# HelvePicV2_0fSMD.net
KiCad netlist of a schematic drawn in EAGLE
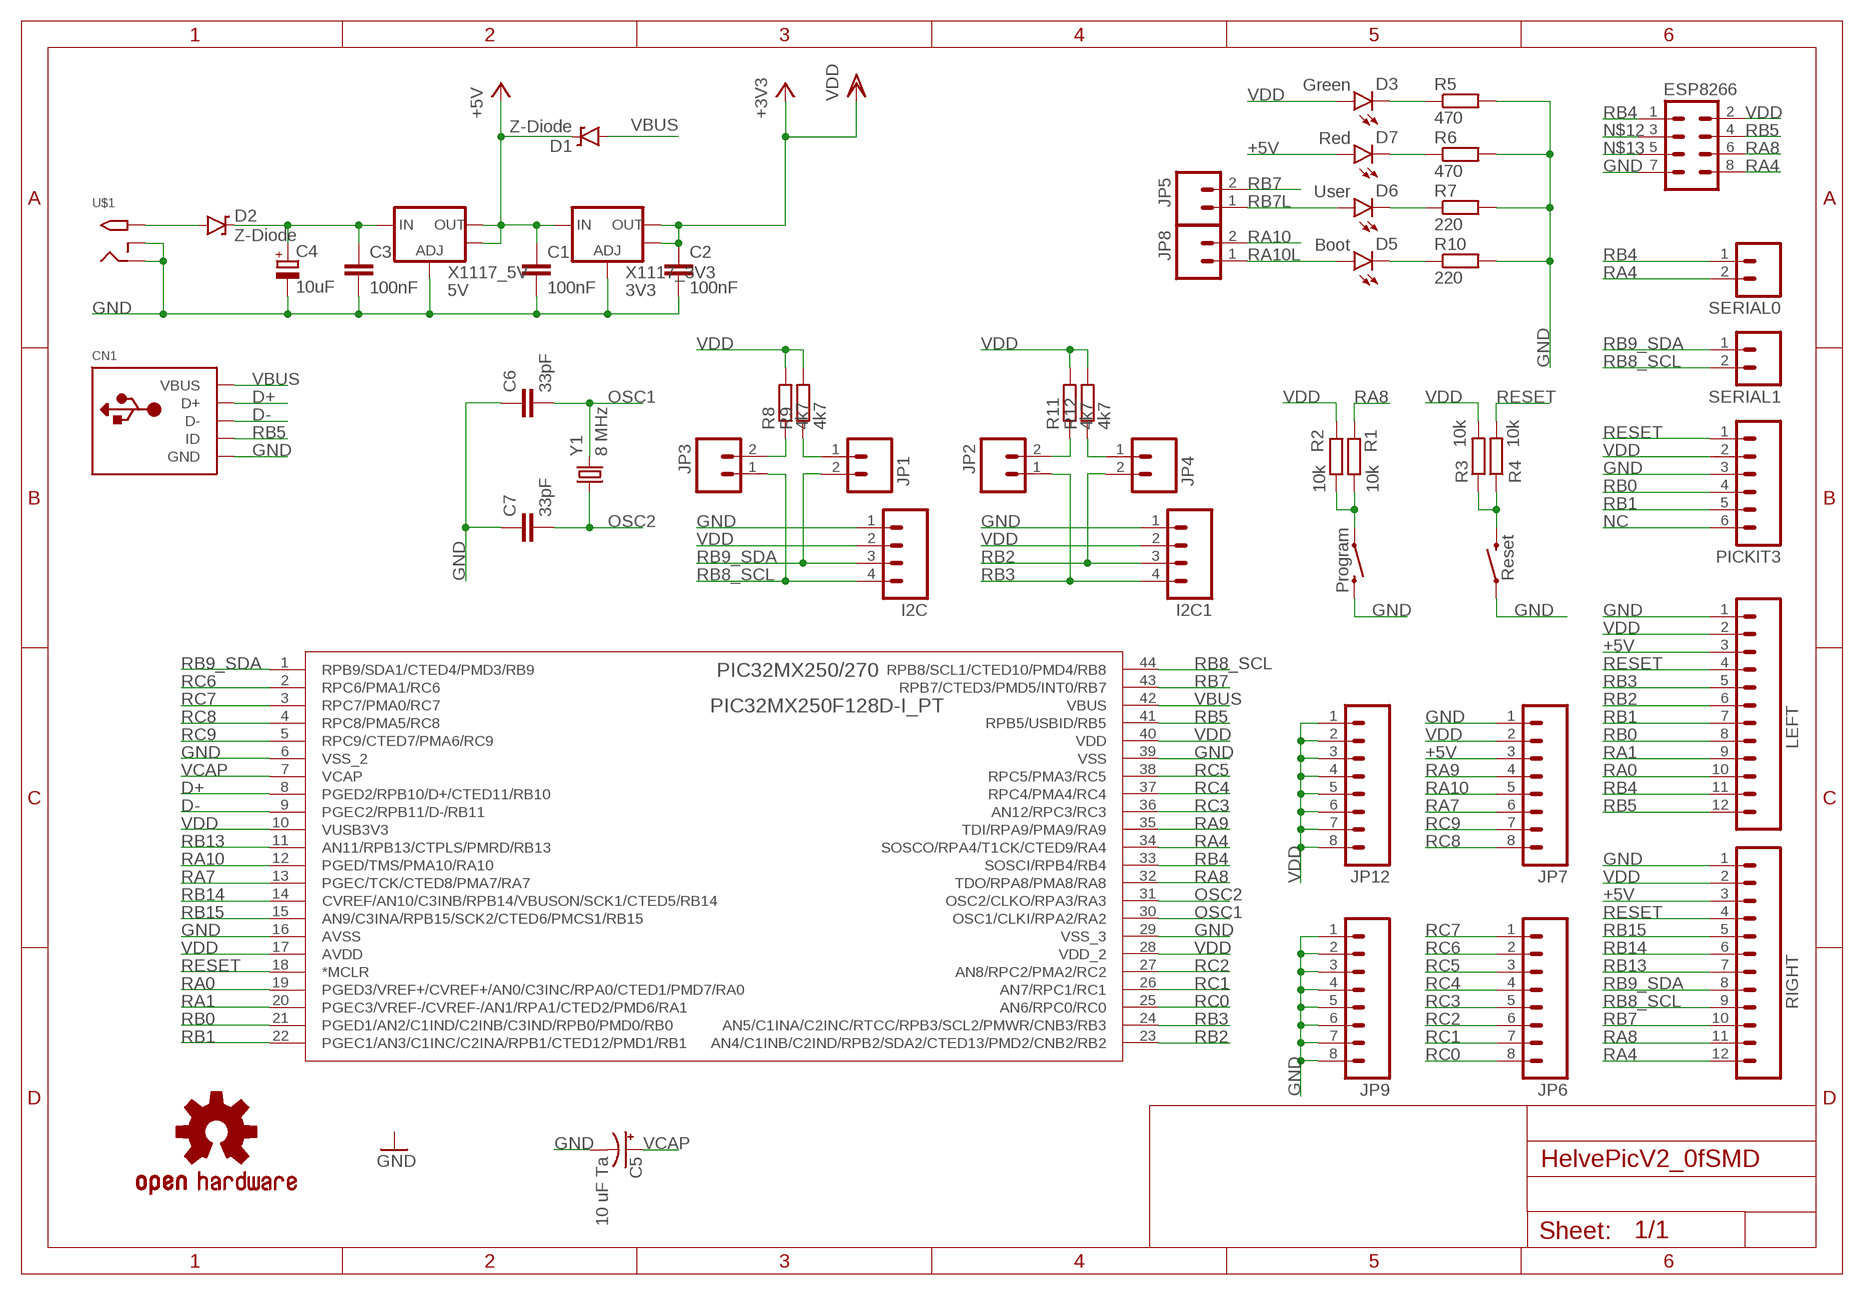
[diagram p0: schematic, sheet 1]

(export (version "E")
  (design (tool "Eeschema 10.0.6"))
  (components
    (comp (ref "C1")
      (value "100nF")
      (footprint "eagle-import:C1206")
      (libsource (lib "eagle-import") (part "C-EUC1206"))
    )
    (comp (ref "C2")
      (value "100nF")
      (footprint "eagle-import:C1206")
      (libsource (lib "eagle-import") (part "C-EUC1206"))
    )
    (comp (ref "C3")
      (value "100nF")
      (footprint "eagle-import:C1206")
      (libsource (lib "eagle-import") (part "C-EUC1206"))
    )
    (comp (ref "C4")
      (value "10uF")
      (footprint "eagle-import:153CLV-0810")
      (libsource (lib "eagle-import") (part "CPOL-EU153CLV-0810"))
    )
    (comp (ref "C5")
      (value "10 uF Ta")
      (footprint "eagle-import:EIA3216")
      (libsource (lib "eagle-import") (part "CAP_POL1206"))
    )
    (comp (ref "C6")
      (value "33pF")
      (footprint "eagle-import:C1206")
      (libsource (lib "eagle-import") (part "C-EUC1206"))
    )
    (comp (ref "C7")
      (value "33pF")
      (footprint "eagle-import:C1206")
      (libsource (lib "eagle-import") (part "C-EUC1206"))
    )
    (comp (ref "CN1")
      (value "USBMINIB")
      (footprint "eagle-import:USB-MINIB")
      (libsource (lib "eagle-import") (part "USBMINIB"))
    )
    (comp (ref "D1")
      (value "Z-Diode")
      (footprint "eagle-import:SMB-DIODE")
      (libsource (lib "eagle-import") (part "DIODE-ZENERSMB"))
    )
    (comp (ref "D2")
      (value "Z-Diode")
      (footprint "eagle-import:SMB-DIODE")
      (libsource (lib "eagle-import") (part "DIODE-ZENERSMB"))
    )
    (comp (ref "D3")
      (value "Green")
      (footprint "eagle-import:LED-1206")
      (libsource (lib "eagle-import") (part "LED1206"))
    )
    (comp (ref "D5")
      (value "Boot")
      (footprint "eagle-import:LED-1206")
      (libsource (lib "eagle-import") (part "LED1206"))
    )
    (comp (ref "D6")
      (value "User")
      (footprint "eagle-import:LED-1206")
      (libsource (lib "eagle-import") (part "LED1206"))
    )
    (comp (ref "D7")
      (value "Red")
      (footprint "eagle-import:LED-1206")
      (libsource (lib "eagle-import") (part "LED1206"))
    )
    (comp (ref "ESP8266")
      (value "M04X2")
      (footprint "eagle-import:2X4")
      (libsource (lib "eagle-import") (part "M04X2"))
    )
    (comp (ref "I2C")
      (value "M04PTH")
      (footprint "eagle-import:1X04")
      (libsource (lib "eagle-import") (part "M04PTH"))
    )
    (comp (ref "I2C1")
      (value "M04PTH")
      (footprint "eagle-import:1X04")
      (libsource (lib "eagle-import") (part "M04PTH"))
    )
    (comp (ref "JP1")
      (value "M02PTH")
      (footprint "eagle-import:1X02")
      (libsource (lib "eagle-import") (part "M02PTH"))
    )
    (comp (ref "JP2")
      (value "M02PTH")
      (footprint "eagle-import:1X02")
      (libsource (lib "eagle-import") (part "M02PTH"))
    )
    (comp (ref "JP3")
      (value "M02PTH")
      (footprint "eagle-import:1X02")
      (libsource (lib "eagle-import") (part "M02PTH"))
    )
    (comp (ref "JP4")
      (value "M02PTH")
      (footprint "eagle-import:1X02")
      (libsource (lib "eagle-import") (part "M02PTH"))
    )
    (comp (ref "JP5")
      (value "M02PTH")
      (footprint "eagle-import:1X02")
      (libsource (lib "eagle-import") (part "M02PTH"))
    )
    (comp (ref "JP6")
      (value "M081X08")
      (footprint "eagle-import:1X08")
      (libsource (lib "eagle-import") (part "M081X08"))
    )
    (comp (ref "JP7")
      (value "M081X08")
      (footprint "eagle-import:1X08")
      (libsource (lib "eagle-import") (part "M081X08"))
    )
    (comp (ref "JP8")
      (value "M02PTH")
      (footprint "eagle-import:1X02")
      (libsource (lib "eagle-import") (part "M02PTH"))
    )
    (comp (ref "JP9")
      (value "M081X08")
      (footprint "eagle-import:1X08")
      (libsource (lib "eagle-import") (part "M081X08"))
    )
    (comp (ref "JP12")
      (value "M081X08")
      (footprint "eagle-import:1X08")
      (libsource (lib "eagle-import") (part "M081X08"))
    )
    (comp (ref "LEFT")
      (value "M12PTH")
      (footprint "eagle-import:1X12")
      (libsource (lib "eagle-import") (part "M12PTH"))
    )
    (comp (ref "LOGO1")
      (value "OSHW-LOGOS")
      (footprint "eagle-import:OSHW-LOGO-S")
      (libsource (lib "eagle-import") (part "OSHW-LOGOS"))
    )
    (comp (ref "PIC32MX250/270")
      (value "PIC32MX250F128D-I_PT")
      (footprint "eagle-import:QFP44_10X10MC")
      (libsource (lib "eagle-import") (part "PIC32MX250F128D-I_PT"))
    )
    (comp (ref "PICKIT3")
      (value "M06LOCK")
      (footprint "eagle-import:1X06_LOCK")
      (libsource (lib "eagle-import") (part "M06LOCK"))
    )
    (comp (ref "R1")
      (value "10k")
      (footprint "eagle-import:R1206")
      (libsource (lib "eagle-import") (part "R-EU_R1206"))
    )
    (comp (ref "R2")
      (value "10k")
      (footprint "eagle-import:R1206")
      (libsource (lib "eagle-import") (part "R-EU_R1206"))
    )
    (comp (ref "R3")
      (value "10k")
      (footprint "eagle-import:R1206")
      (libsource (lib "eagle-import") (part "R-EU_R1206"))
    )
    (comp (ref "R4")
      (value "10k")
      (footprint "eagle-import:R1206")
      (libsource (lib "eagle-import") (part "R-EU_R1206"))
    )
    (comp (ref "R5")
      (value "470")
      (footprint "eagle-import:R1206")
      (libsource (lib "eagle-import") (part "R-EU_R1206"))
    )
    (comp (ref "R6")
      (value "470")
      (footprint "eagle-import:R1206")
      (libsource (lib "eagle-import") (part "R-EU_R1206"))
    )
    (comp (ref "R7")
      (value "220")
      (footprint "eagle-import:R1206")
      (libsource (lib "eagle-import") (part "R-EU_R1206"))
    )
    (comp (ref "R8")
      (value "4k7")
      (footprint "eagle-import:R1206")
      (libsource (lib "eagle-import") (part "R-EU_R1206"))
    )
    (comp (ref "R9")
      (value "4k7")
      (footprint "eagle-import:R1206")
      (libsource (lib "eagle-import") (part "R-EU_R1206"))
    )
    (comp (ref "R10")
      (value "220")
      (footprint "eagle-import:R1206")
      (libsource (lib "eagle-import") (part "R-EU_R1206"))
    )
    (comp (ref "R11")
      (value "4k7")
      (footprint "eagle-import:R1206")
      (libsource (lib "eagle-import") (part "R-EU_R1206"))
    )
    (comp (ref "R12")
      (value "4k7")
      (footprint "eagle-import:R1206")
      (libsource (lib "eagle-import") (part "R-EU_R1206"))
    )
    (comp (ref "RIGHT")
      (value "M12PTH")
      (footprint "eagle-import:1X12")
      (libsource (lib "eagle-import") (part "M12PTH"))
    )
    (comp (ref "S1")
      (value "Program")
      (footprint "eagle-import:TACTILE_SWITCH_TALL")
      (libsource (lib "eagle-import") (part "SWITCH-MOMENTARY-2SMD-4"))
    )
    (comp (ref "S3")
      (value "Reset")
      (footprint "eagle-import:TACTILE_SWITCH_TALL")
      (libsource (lib "eagle-import") (part "SWITCH-MOMENTARY-2SMD-4"))
    )
    (comp (ref "SERIAL0")
      (value "M02PTH")
      (footprint "eagle-import:1X02")
      (libsource (lib "eagle-import") (part "M02PTH"))
    )
    (comp (ref "SERIAL1")
      (value "M02PTH")
      (footprint "eagle-import:1X02")
      (libsource (lib "eagle-import") (part "M02PTH"))
    )
    (comp (ref "U$1")
      (value "2.1MMJACKTHM")
      (footprint "eagle-import:PJ-102A")
      (libsource (lib "eagle-import") (part "2.1MMJACKTHM"))
    )
    (comp (ref "X1117_3V3")
      (value "3V3")
      (footprint "eagle-import:SOT223")
      (libsource (lib "eagle-import") (part "V_REG_LM1117SOT223"))
    )
    (comp (ref "X1117_5V")
      (value "5V")
      (footprint "eagle-import:SOT223")
      (libsource (lib "eagle-import") (part "V_REG_LM1117SOT223"))
    )
    (comp (ref "Y1")
      (value "8 MHz")
      (footprint "eagle-import:HC49UP")
      (libsource (lib "eagle-import") (part "CRYSTALSMD"))
    )
  )
  (nets
    (net (code "1") (name "+3V3") (class "Default")
      (node (ref "C2") (pin "1") (pinfunction "1_1") (pintype "passive"))
      (node (ref "D3") (pin "A") (pinfunction "A_A") (pintype "passive"))
      (node (ref "ESP8266") (pin "2") (pinfunction "2_2") (pintype "passive"))
      (node (ref "I2C") (pin "2") (pinfunction "2_2") (pintype "passive"))
      (node (ref "I2C1") (pin "2") (pinfunction "2_2") (pintype "passive"))
      (node (ref "JP12") (pin "1") (pinfunction "1_1") (pintype "passive"))
      (node (ref "JP12") (pin "2") (pinfunction "2_2") (pintype "passive"))
      (node (ref "JP12") (pin "3") (pinfunction "3_3") (pintype "passive"))
      (node (ref "JP12") (pin "4") (pinfunction "4_4") (pintype "passive"))
      (node (ref "JP12") (pin "5") (pinfunction "5_5") (pintype "passive"))
      (node (ref "JP12") (pin "6") (pinfunction "6_6") (pintype "passive"))
      (node (ref "JP12") (pin "7") (pinfunction "7_7") (pintype "passive"))
      (node (ref "JP12") (pin "8") (pinfunction "8_8") (pintype "passive"))
      (node (ref "JP7") (pin "2") (pinfunction "2_2") (pintype "passive"))
      (node (ref "LEFT") (pin "2") (pinfunction "2_2") (pintype "passive"))
      (node (ref "PIC32MX250/270") (pin "10") (pinfunction "VUSB3V3_10") (pintype "bidirectional"))
      (node (ref "PIC32MX250/270") (pin "17") (pinfunction "AVDD_17") (pintype "power_in"))
      (node (ref "PIC32MX250/270") (pin "28") (pinfunction "VDD_2_28") (pintype "power_in"))
      (node (ref "PIC32MX250/270") (pin "40") (pinfunction "VDD_40") (pintype "power_in"))
      (node (ref "PICKIT3") (pin "2") (pinfunction "2_2") (pintype "passive"))
      (node (ref "R11") (pin "2") (pinfunction "2_2") (pintype "passive"))
      (node (ref "R12") (pin "2") (pinfunction "2_2") (pintype "passive"))
      (node (ref "R2") (pin "1") (pinfunction "1_1") (pintype "passive"))
      (node (ref "R3") (pin "2") (pinfunction "2_2") (pintype "passive"))
      (node (ref "R8") (pin "2") (pinfunction "2_2") (pintype "passive"))
      (node (ref "R9") (pin "2") (pinfunction "2_2") (pintype "passive"))
      (node (ref "RIGHT") (pin "2") (pinfunction "2_2") (pintype "passive"))
      (node (ref "X1117_3V3") (pin "2") (pinfunction "OUT_2") (pintype "output"))
      (node (ref "X1117_3V3") (pin "4") (pinfunction "OUT_4") (pintype "output"))
    )
    (net (code "2") (name "+5V") (class "Default")
      (node (ref "C1") (pin "1") (pinfunction "1_1") (pintype "passive"))
      (node (ref "D1") (pin "C") (pinfunction "C_C") (pintype "passive"))
      (node (ref "D7") (pin "A") (pinfunction "A_A") (pintype "passive"))
      (node (ref "JP7") (pin "3") (pinfunction "3_3") (pintype "passive"))
      (node (ref "LEFT") (pin "3") (pinfunction "3_3") (pintype "passive"))
      (node (ref "RIGHT") (pin "3") (pinfunction "3_3") (pintype "passive"))
      (node (ref "X1117_3V3") (pin "3") (pinfunction "IN_3") (pintype "input"))
      (node (ref "X1117_5V") (pin "2") (pinfunction "OUT_2") (pintype "output"))
      (node (ref "X1117_5V") (pin "4") (pinfunction "OUT_4") (pintype "output"))
    )
    (net (code "3") (name "/D+") (class "Default")
      (node (ref "CN1") (pin "D+") (pinfunction "D+_D+") (pintype "bidirectional"))
      (node (ref "PIC32MX250/270") (pin "8") (pinfunction "PGED2/RPB10/D+/CTED11/RB10_8") (pintype "bidirectional"))
    )
    (net (code "4") (name "/D-") (class "Default")
      (node (ref "CN1") (pin "D-") (pinfunction "D-_D-") (pintype "bidirectional"))
      (node (ref "PIC32MX250/270") (pin "9") (pinfunction "PGEC2/RPB11/D-/RB11_9") (pintype "bidirectional"))
    )
    (net (code "5") (name "/N$12") (class "Default")
      (node (ref "ESP8266") (pin "3") (pinfunction "3_3") (pintype "passive"))
    )
    (net (code "6") (name "/N$13") (class "Default")
      (node (ref "ESP8266") (pin "5") (pinfunction "5_5") (pintype "passive"))
    )
    (net (code "7") (name "/NC") (class "Default")
      (node (ref "PICKIT3") (pin "6") (pinfunction "6_6") (pintype "passive"))
    )
    (net (code "8") (name "/OSC1") (class "Default")
      (node (ref "C6") (pin "2") (pinfunction "2_2") (pintype "passive"))
      (node (ref "PIC32MX250/270") (pin "30") (pinfunction "OSC1/CLKI/RPA2/RA2_30") (pintype "bidirectional"))
      (node (ref "Y1") (pin "2") (pinfunction "2_2") (pintype "passive"))
    )
    (net (code "9") (name "/OSC2") (class "Default")
      (node (ref "C7") (pin "2") (pinfunction "2_2") (pintype "passive"))
      (node (ref "PIC32MX250/270") (pin "31") (pinfunction "OSC2/CLKO/RPA3/RA3_31") (pintype "bidirectional"))
      (node (ref "Y1") (pin "1") (pinfunction "1_1") (pintype "passive"))
    )
    (net (code "10") (name "/RA0") (class "Default")
      (node (ref "LEFT") (pin "10") (pinfunction "10_10") (pintype "passive"))
      (node (ref "PIC32MX250/270") (pin "19") (pinfunction "PGED3/VREF+/CVREF+/AN0/C3INC/RPA0/CTED1/PMD7/RA0_19") (pintype "bidirectional"))
    )
    (net (code "11") (name "/RA1") (class "Default")
      (node (ref "LEFT") (pin "9") (pinfunction "9_9") (pintype "passive"))
      (node (ref "PIC32MX250/270") (pin "20") (pinfunction "PGEC3/VREF-/CVREF-/AN1/RPA1/CTED2/PMD6/RA1_20") (pintype "bidirectional"))
    )
    (net (code "12") (name "/RA4") (class "Default")
      (node (ref "ESP8266") (pin "8") (pinfunction "8_8") (pintype "passive"))
      (node (ref "PIC32MX250/270") (pin "34") (pinfunction "SOSCO/RPA4/T1CK/CTED9/RA4_34") (pintype "bidirectional"))
      (node (ref "RIGHT") (pin "12") (pinfunction "12_12") (pintype "passive"))
      (node (ref "SERIAL0") (pin "2") (pinfunction "2_2") (pintype "passive"))
    )
    (net (code "13") (name "/RA7") (class "Default")
      (node (ref "JP7") (pin "6") (pinfunction "6_6") (pintype "passive"))
      (node (ref "PIC32MX250/270") (pin "13") (pinfunction "PGEC/TCK/CTED8/PMA7/RA7_13") (pintype "bidirectional"))
    )
    (net (code "14") (name "/RA8") (class "Default")
      (node (ref "ESP8266") (pin "6") (pinfunction "6_6") (pintype "passive"))
      (node (ref "PIC32MX250/270") (pin "32") (pinfunction "TDO/RPA8/PMA8/RA8_32") (pintype "bidirectional"))
      (node (ref "R1") (pin "1") (pinfunction "1_1") (pintype "passive"))
      (node (ref "RIGHT") (pin "11") (pinfunction "11_11") (pintype "passive"))
    )
    (net (code "15") (name "/RA9") (class "Default")
      (node (ref "JP7") (pin "4") (pinfunction "4_4") (pintype "passive"))
      (node (ref "PIC32MX250/270") (pin "35") (pinfunction "TDI/RPA9/PMA9/RA9_35") (pintype "bidirectional"))
    )
    (net (code "16") (name "/RA10") (class "Default")
      (node (ref "JP7") (pin "5") (pinfunction "5_5") (pintype "passive"))
      (node (ref "JP8") (pin "2") (pinfunction "2_2") (pintype "passive"))
      (node (ref "PIC32MX250/270") (pin "12") (pinfunction "PGED/TMS/PMA10/RA10_12") (pintype "bidirectional"))
    )
    (net (code "17") (name "/RA10L") (class "Default")
      (node (ref "D5") (pin "A") (pinfunction "A_A") (pintype "passive"))
      (node (ref "JP8") (pin "1") (pinfunction "1_1") (pintype "passive"))
    )
    (net (code "18") (name "/RB0") (class "Default")
      (node (ref "LEFT") (pin "8") (pinfunction "8_8") (pintype "passive"))
      (node (ref "PIC32MX250/270") (pin "21") (pinfunction "PGED1/AN2/C1IND/C2INB/C3IND/RPB0/PMD0/RB0_21") (pintype "bidirectional"))
      (node (ref "PICKIT3") (pin "4") (pinfunction "4_4") (pintype "passive"))
    )
    (net (code "19") (name "/RB1") (class "Default")
      (node (ref "LEFT") (pin "7") (pinfunction "7_7") (pintype "passive"))
      (node (ref "PIC32MX250/270") (pin "22") (pinfunction "PGEC1/AN3/C1INC/C2INA/RPB1/CTED12/PMD1/RB1_22") (pintype "bidirectional"))
      (node (ref "PICKIT3") (pin "5") (pinfunction "5_5") (pintype "passive"))
    )
    (net (code "20") (name "/RB2") (class "Default")
      (node (ref "I2C1") (pin "3") (pinfunction "3_3") (pintype "passive"))
      (node (ref "JP4") (pin "2") (pinfunction "2_2") (pintype "passive"))
      (node (ref "LEFT") (pin "6") (pinfunction "6_6") (pintype "passive"))
      (node (ref "PIC32MX250/270") (pin "23") (pinfunction "AN4/C1INB/C2IND/RPB2/SDA2/CTED13/PMD2/CNB2/RB2_23") (pintype "bidirectional"))
    )
    (net (code "21") (name "/RB3") (class "Default")
      (node (ref "I2C1") (pin "4") (pinfunction "4_4") (pintype "passive"))
      (node (ref "JP2") (pin "1") (pinfunction "1_1") (pintype "passive"))
      (node (ref "LEFT") (pin "5") (pinfunction "5_5") (pintype "passive"))
      (node (ref "PIC32MX250/270") (pin "24") (pinfunction "AN5/C1INA/C2INC/RTCC/RPB3/SCL2/PMWR/CNB3/RB3_24") (pintype "bidirectional"))
    )
    (net (code "22") (name "/RB4") (class "Default")
      (node (ref "ESP8266") (pin "1") (pinfunction "1_1") (pintype "passive"))
      (node (ref "LEFT") (pin "11") (pinfunction "11_11") (pintype "passive"))
      (node (ref "PIC32MX250/270") (pin "33") (pinfunction "SOSCI/RPB4/RB4_33") (pintype "bidirectional"))
      (node (ref "SERIAL0") (pin "1") (pinfunction "1_1") (pintype "passive"))
    )
    (net (code "23") (name "/RB5") (class "Default")
      (node (ref "CN1") (pin "ID") (pinfunction "ID_ID") (pintype "bidirectional"))
      (node (ref "ESP8266") (pin "4") (pinfunction "4_4") (pintype "passive"))
      (node (ref "LEFT") (pin "12") (pinfunction "12_12") (pintype "passive"))
      (node (ref "PIC32MX250/270") (pin "41") (pinfunction "RPB5/USBID/RB5_41") (pintype "bidirectional"))
    )
    (net (code "24") (name "/RB7") (class "Default")
      (node (ref "JP5") (pin "2") (pinfunction "2_2") (pintype "passive"))
      (node (ref "PIC32MX250/270") (pin "43") (pinfunction "RPB7/CTED3/PMD5/INT0/RB7_43") (pintype "bidirectional"))
      (node (ref "RIGHT") (pin "10") (pinfunction "10_10") (pintype "passive"))
    )
    (net (code "25") (name "/RB7L") (class "Default")
      (node (ref "D6") (pin "A") (pinfunction "A_A") (pintype "passive"))
      (node (ref "JP5") (pin "1") (pinfunction "1_1") (pintype "passive"))
    )
    (net (code "26") (name "/RB8_SCL") (class "Default")
      (node (ref "I2C") (pin "4") (pinfunction "4_4") (pintype "passive"))
      (node (ref "JP3") (pin "1") (pinfunction "1_1") (pintype "passive"))
      (node (ref "PIC32MX250/270") (pin "44") (pinfunction "RPB8/SCL1/CTED10/PMD4/RB8_44") (pintype "bidirectional"))
      (node (ref "RIGHT") (pin "9") (pinfunction "9_9") (pintype "passive"))
      (node (ref "SERIAL1") (pin "2") (pinfunction "2_2") (pintype "passive"))
    )
    (net (code "27") (name "/RB9_SDA") (class "Default")
      (node (ref "I2C") (pin "3") (pinfunction "3_3") (pintype "passive"))
      (node (ref "JP1") (pin "2") (pinfunction "2_2") (pintype "passive"))
      (node (ref "PIC32MX250/270") (pin "1") (pinfunction "RPB9/SDA1/CTED4/PMD3/RB9_1") (pintype "bidirectional"))
      (node (ref "RIGHT") (pin "8") (pinfunction "8_8") (pintype "passive"))
      (node (ref "SERIAL1") (pin "1") (pinfunction "1_1") (pintype "passive"))
    )
    (net (code "28") (name "/RB13") (class "Default")
      (node (ref "PIC32MX250/270") (pin "11") (pinfunction "AN11/RPB13/CTPLS/PMRD/RB13_11") (pintype "bidirectional"))
      (node (ref "RIGHT") (pin "7") (pinfunction "7_7") (pintype "passive"))
    )
    (net (code "29") (name "/RB14") (class "Default")
      (node (ref "PIC32MX250/270") (pin "14") (pinfunction "CVREF/AN10/C3INB/RPB14/VBUSON/SCK1/CTED5/RB14_14") (pintype "bidirectional"))
      (node (ref "RIGHT") (pin "6") (pinfunction "6_6") (pintype "passive"))
    )
    (net (code "30") (name "/RB15") (class "Default")
      (node (ref "PIC32MX250/270") (pin "15") (pinfunction "AN9/C3INA/RPB15/SCK2/CTED6/PMCS1/RB15_15") (pintype "bidirectional"))
      (node (ref "RIGHT") (pin "5") (pinfunction "5_5") (pintype "passive"))
    )
    (net (code "31") (name "/RC0") (class "Default")
      (node (ref "JP6") (pin "8") (pinfunction "8_8") (pintype "passive"))
      (node (ref "PIC32MX250/270") (pin "25") (pinfunction "AN6/RPC0/RC0_25") (pintype "bidirectional"))
    )
    (net (code "32") (name "/RC1") (class "Default")
      (node (ref "JP6") (pin "7") (pinfunction "7_7") (pintype "passive"))
      (node (ref "PIC32MX250/270") (pin "26") (pinfunction "AN7/RPC1/RC1_26") (pintype "bidirectional"))
    )
    (net (code "33") (name "/RC2") (class "Default")
      (node (ref "JP6") (pin "6") (pinfunction "6_6") (pintype "passive"))
      (node (ref "PIC32MX250/270") (pin "27") (pinfunction "AN8/RPC2/PMA2/RC2_27") (pintype "bidirectional"))
    )
    (net (code "34") (name "/RC3") (class "Default")
      (node (ref "JP6") (pin "5") (pinfunction "5_5") (pintype "passive"))
      (node (ref "PIC32MX250/270") (pin "36") (pinfunction "AN12/RPC3/RC3_36") (pintype "bidirectional"))
    )
    (net (code "35") (name "/RC4") (class "Default")
      (node (ref "JP6") (pin "4") (pinfunction "4_4") (pintype "passive"))
      (node (ref "PIC32MX250/270") (pin "37") (pinfunction "RPC4/PMA4/RC4_37") (pintype "bidirectional"))
    )
    (net (code "36") (name "/RC5") (class "Default")
      (node (ref "JP6") (pin "3") (pinfunction "3_3") (pintype "passive"))
      (node (ref "PIC32MX250/270") (pin "38") (pinfunction "RPC5/PMA3/RC5_38") (pintype "bidirectional"))
    )
    (net (code "37") (name "/RC6") (class "Default")
      (node (ref "JP6") (pin "2") (pinfunction "2_2") (pintype "passive"))
      (node (ref "PIC32MX250/270") (pin "2") (pinfunction "RPC6/PMA1/RC6_2") (pintype "bidirectional"))
    )
    (net (code "38") (name "/RC7") (class "Default")
      (node (ref "JP6") (pin "1") (pinfunction "1_1") (pintype "passive"))
      (node (ref "PIC32MX250/270") (pin "3") (pinfunction "RPC7/PMA0/RC7_3") (pintype "bidirectional"))
    )
    (net (code "39") (name "/RC8") (class "Default")
      (node (ref "JP7") (pin "8") (pinfunction "8_8") (pintype "passive"))
      (node (ref "PIC32MX250/270") (pin "4") (pinfunction "RPC8/PMA5/RC8_4") (pintype "bidirectional"))
    )
    (net (code "40") (name "/RC9") (class "Default")
      (node (ref "JP7") (pin "7") (pinfunction "7_7") (pintype "passive"))
      (node (ref "PIC32MX250/270") (pin "5") (pinfunction "RPC9/CTED7/PMA6/RC9_5") (pintype "bidirectional"))
    )
    (net (code "41") (name "/RESET") (class "Default")
      (node (ref "LEFT") (pin "4") (pinfunction "4_4") (pintype "passive"))
      (node (ref "PIC32MX250/270") (pin "18") (pinfunction "*MCLR_18") (pintype "input"))
      (node (ref "PICKIT3") (pin "1") (pinfunction "1_1") (pintype "passive"))
      (node (ref "R4") (pin "2") (pinfunction "2_2") (pintype "passive"))
      (node (ref "RIGHT") (pin "4") (pinfunction "4_4") (pintype "passive"))
    )
    (net (code "42") (name "/VBUS") (class "Default")
      (node (ref "CN1") (pin "VBUS") (pinfunction "VBUS_VBUS") (pintype "power_in"))
      (node (ref "D1") (pin "A") (pinfunction "A_A") (pintype "passive"))
      (node (ref "PIC32MX250/270") (pin "42") (pinfunction "VBUS_42") (pintype "power_in"))
    )
    (net (code "43") (name "/VCAP") (class "Default")
      (node (ref "C5") (pin "A") (pinfunction "+_A") (pintype "passive"))
      (node (ref "PIC32MX250/270") (pin "7") (pinfunction "VCAP_7") (pintype "power_in"))
    )
    (net (code "44") (name "GND") (class "Default")
      (node (ref "C1") (pin "2") (pinfunction "2_2") (pintype "passive"))
      (node (ref "C2") (pin "2") (pinfunction "2_2") (pintype "passive"))
      (node (ref "C3") (pin "2") (pinfunction "2_2") (pintype "passive"))
      (node (ref "C4") (pin "-") (pinfunction "-_-") (pintype "passive"))
      (node (ref "C5") (pin "C") (pinfunction "-_C") (pintype "passive"))
      (node (ref "C6") (pin "1") (pinfunction "1_1") (pintype "passive"))
      (node (ref "C7") (pin "1") (pinfunction "1_1") (pintype "passive"))
      (node (ref "CN1") (pin "GND") (pinfunction "GND_GND") (pintype "power_in"))
      (node (ref "ESP8266") (pin "7") (pinfunction "7_7") (pintype "passive"))
      (node (ref "I2C") (pin "1") (pinfunction "1_1") (pintype "passive"))
      (node (ref "I2C1") (pin "1") (pinfunction "1_1") (pintype "passive"))
      (node (ref "JP7") (pin "1") (pinfunction "1_1") (pintype "passive"))
      (node (ref "JP9") (pin "1") (pinfunction "1_1") (pintype "passive"))
      (node (ref "JP9") (pin "2") (pinfunction "2_2") (pintype "passive"))
      (node (ref "JP9") (pin "3") (pinfunction "3_3") (pintype "passive"))
      (node (ref "JP9") (pin "4") (pinfunction "4_4") (pintype "passive"))
      (node (ref "JP9") (pin "5") (pinfunction "5_5") (pintype "passive"))
      (node (ref "JP9") (pin "6") (pinfunction "6_6") (pintype "passive"))
      (node (ref "JP9") (pin "7") (pinfunction "7_7") (pintype "passive"))
      (node (ref "JP9") (pin "8") (pinfunction "8_8") (pintype "passive"))
      (node (ref "LEFT") (pin "1") (pinfunction "1_1") (pintype "passive"))
      (node (ref "PIC32MX250/270") (pin "16") (pinfunction "AVSS_16") (pintype "power_in"))
      (node (ref "PIC32MX250/270") (pin "29") (pinfunction "VSS_3_29") (pintype "power_in"))
      (node (ref "PIC32MX250/270") (pin "39") (pinfunction "VSS_39") (pintype "power_in"))
      (node (ref "PIC32MX250/270") (pin "6") (pinfunction "VSS_2_6") (pintype "power_in"))
      (node (ref "PICKIT3") (pin "3") (pinfunction "3_3") (pintype "passive"))
      (node (ref "R10") (pin "2") (pinfunction "2_2") (pintype "passive"))
      (node (ref "R5") (pin "2") (pinfunction "2_2") (pintype "passive"))
      (node (ref "R6") (pin "2") (pinfunction "2_2") (pintype "passive"))
      (node (ref "R7") (pin "2") (pinfunction "2_2") (pintype "passive"))
      (node (ref "RIGHT") (pin "1") (pinfunction "1_1") (pintype "passive"))
      (node (ref "S1") (pin "B2") (pinfunction "2_B2") (pintype "passive"))
      (node (ref "S3") (pin "A2") (pinfunction "1_A2") (pintype "passive"))
      (node (ref "U$1") (pin "RING") (pinfunction "RING_RING") (pintype "bidirectional"))
      (node (ref "U$1") (pin "RING_SW") (pinfunction "RING_SW_RING_SW") (pintype "bidirectional"))
      (node (ref "X1117_3V3") (pin "1") (pinfunction "ADJ_1") (pintype "input"))
      (node (ref "X1117_5V") (pin "1") (pinfunction "ADJ_1") (pintype "input"))
    )
    (net (code "45") (name "Net-(D2-PadA)") (class "Default")
      (node (ref "D2") (pin "A") (pinfunction "A_A") (pintype "passive"))
      (node (ref "U$1") (pin "TIP") (pinfunction "TIP_TIP") (pintype "bidirectional"))
    )
    (net (code "46") (name "Net-(D3-PadC)") (class "Default")
      (node (ref "D3") (pin "C") (pinfunction "C_C") (pintype "passive"))
      (node (ref "R5") (pin "1") (pinfunction "1_1") (pintype "passive"))
    )
    (net (code "47") (name "Net-(D5-PadC)") (class "Default")
      (node (ref "D5") (pin "C") (pinfunction "C_C") (pintype "passive"))
      (node (ref "R10") (pin "1") (pinfunction "1_1") (pintype "passive"))
    )
    (net (code "48") (name "Net-(D6-PadC)") (class "Default")
      (node (ref "D6") (pin "C") (pinfunction "C_C") (pintype "passive"))
      (node (ref "R7") (pin "1") (pinfunction "1_1") (pintype "passive"))
    )
    (net (code "49") (name "Net-(D7-PadC)") (class "Default")
      (node (ref "D7") (pin "C") (pinfunction "C_C") (pintype "passive"))
      (node (ref "R6") (pin "1") (pinfunction "1_1") (pintype "passive"))
    )
    (net (code "50") (name "Net-(JP1-Pad1)") (class "Default")
      (node (ref "JP1") (pin "1") (pinfunction "1_1") (pintype "passive"))
      (node (ref "R9") (pin "1") (pinfunction "1_1") (pintype "passive"))
    )
    (net (code "51") (name "Net-(JP2-Pad2)") (class "Default")
      (node (ref "JP2") (pin "2") (pinfunction "2_2") (pintype "passive"))
      (node (ref "R11") (pin "1") (pinfunction "1_1") (pintype "passive"))
    )
    (net (code "52") (name "Net-(JP3-Pad2)") (class "Default")
      (node (ref "JP3") (pin "2") (pinfunction "2_2") (pintype "passive"))
      (node (ref "R8") (pin "1") (pinfunction "1_1") (pintype "passive"))
    )
    (net (code "53") (name "Net-(JP4-Pad1)") (class "Default")
      (node (ref "JP4") (pin "1") (pinfunction "1_1") (pintype "passive"))
      (node (ref "R12") (pin "1") (pinfunction "1_1") (pintype "passive"))
    )
    (net (code "54") (name "Net-(S1-1)") (class "Default")
      (node (ref "R1") (pin "2") (pinfunction "2_2") (pintype "passive"))
      (node (ref "R2") (pin "2") (pinfunction "2_2") (pintype "passive"))
      (node (ref "S1") (pin "A2") (pinfunction "1_A2") (pintype "passive"))
    )
    (net (code "55") (name "Net-(S3-2)") (class "Default")
      (node (ref "R3") (pin "1") (pinfunction "1_1") (pintype "passive"))
      (node (ref "R4") (pin "1") (pinfunction "1_1") (pintype "passive"))
      (node (ref "S3") (pin "B2") (pinfunction "2_B2") (pintype "passive"))
    )
    (net (code "56") (name "Net-(X1117_5V-IN)") (class "Default")
      (node (ref "C3") (pin "1") (pinfunction "1_1") (pintype "passive"))
      (node (ref "C4") (pin "+") (pinfunction "+_+") (pintype "passive"))
      (node (ref "D2") (pin "C") (pinfunction "C_C") (pintype "passive"))
      (node (ref "X1117_5V") (pin "3") (pinfunction "IN_3") (pintype "input"))
    )
  )
)
